# S7_LoRa.net
KiCad netlist of a schematic drawn in Altium Designer
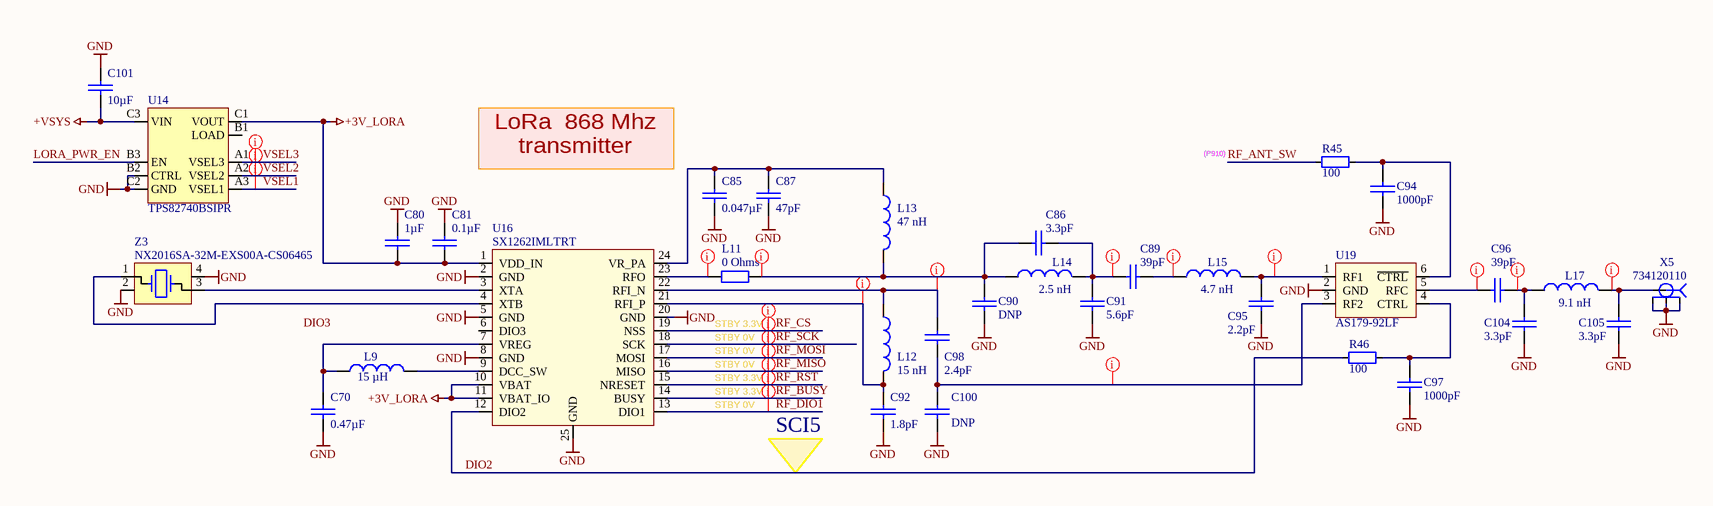
[diagram p0: S7_LoRa.SchDoc]

(export (version "E")
  (design (tool "Eeschema 10.0.6"))
  (components
    (comp (ref "C70")
      (value "0.47µF")
      (footprint "0402 CAP")
      (description "0.47µF, ±20%, 25V, X5R, 0402 (1005 Metric), -55°C ~ 85°C, -, Automotive")
      (fields
        (field (name "PART NUMBER") "GRT155R61E474ME01D")
        (field (name "MANUFACTURER") "Murata Electronics North America")
      )
      (libsource (lib "ea_PassivComps") (part "Capacitor"))
    )
    (comp (ref "C80")
      (value "1µF")
      (footprint "0402 CAP")
      (description "1µF, ±20%, 25V, X5R, 0402 (1005 Metric), -55°C ~ 85°C, -, General Purpose")
      (fields (field (name "PART NUMBER") "TMK105BJ105MV-F") (field (name "MANUFACTURER") "Taiyo Yuden"))
      (libsource (lib "ea_PassivComps") (part "Capacitor"))
    )
    (comp (ref "C81")
      (value "0.1µF")
      (footprint "0402 CAP")
      (description "0.1µF, ±10%, 50V, X7R, 0402 (1005 Metric), -55°C ~ 125°C, -, General Purpose")
      (fields
        (field (name "PART NUMBER") "0402B104K500CT")
        (field (name "MANUFACTURER") "Walsin Technology Corporation")
      )
      (libsource (lib "ea_PassivComps") (part "Capacitor"))
    )
    (comp (ref "C85")
      (value "0.047µF")
      (footprint "0402 CAP")
      (description "0.047µF, ±10%, 25V, X7R, 0402 (1005 Metric), -55°C ~ 125°C, -, General Purpose")
      (fields (field (name "PART NUMBER") "CC0402KRX7R8BB473") (field (name "MANUFACTURER") "Yageo"))
      (libsource (lib "ea_PassivComps") (part "Capacitor"))
    )
    (comp (ref "C86")
      (value "3.3pF")
      (footprint "0402 CAP")
      (description "3.3pF, ±0.1pF, 50V, C0G, NP0, 0402 (1005 Metric), -55°C ~ 125°C, -, RF, Microwave, High Frequency")
      (fields
        (field (name "PART NUMBER") "885392005011")
        (field (name "MANUFACTURER") "Wurth Electronics Inc.")
      )
      (libsource (lib "ea_PassivComps") (part "Capacitor"))
    )
    (comp (ref "C87")
      (value "47pF")
      (footprint "0402 CAP")
      (fields
        (field (name "PART NUMBER") "GJM1555C1H470FB01D")
        (field (name "MANUFACTURER") "Murata Electronics North America")
        (field (name "PARTNUM") "490-16376-1-ND")
      )
      (libsource (lib "ea_PassivComps") (part "Capacitor"))
    )
    (comp (ref "C89")
      (value "39pF")
      (footprint "0402 CAP")
      (fields
        (field (name "PART NUMBER") "GJM1555C1H390JB01D")
        (field (name "MANUFACTURER") "Murata Electronics North America")
        (field (name "PARTNUM") "490-17673-1-ND")
      )
      (libsource (lib "ea_PassivComps") (part "Capacitor"))
    )
    (comp (ref "C90")
      (value "DNP")
      (footprint "0402 CAP")
      (fields (field (name "Comment") "Capacitor_0402"))
      (libsource (lib "ea_Capacitors") (part "Capacitor_0402"))
    )
    (comp (ref "C91")
      (value "5.6pF")
      (footprint "0402 CAP")
      (fields
        (field (name "PART NUMBER") "GJM1555C1H5R6BB01D")
        (field (name "MANUFACTURER") "Murata Electronics North America")
        (field (name "PARTNUM") "490-11225-1-ND")
      )
      (libsource (lib "ea_PassivComps") (part "Capacitor"))
    )
    (comp (ref "C92")
      (value "1.8pF")
      (footprint "0402 CAP")
      (fields
        (field (name "PART NUMBER") "GJM1555C1H1R8BB01D")
        (field (name "MANUFACTURER") "Murata Electronics North America")
        (field (name "PARTNUM") "490-8089-1-ND")
      )
      (libsource (lib "ea_PassivComps") (part "Capacitor"))
    )
    (comp (ref "C94")
      (value "1000pF")
      (footprint "0402 CAP")
      (description "1000pF, ±5%, 50V, CH, 0402 (1005 Metric), -25°C ~ 85°C, Low ESL, General Purpose")
      (fields
        (field (name "PART NUMBER") "C1005CH1H102J050BA")
        (field (name "MANUFACTURER") "TDK Corporation")
      )
      (libsource (lib "ea_PassivComps") (part "Capacitor"))
    )
    (comp (ref "C95")
      (value "2.2pF")
      (footprint "0402 CAP")
      (fields
        (field (name "PART NUMBER") "CBR04C229B5GAC")
        (field (name "MANUFACTURER") "KEMET")
        (field (name "PARTNUM") "399-17527-1-ND")
      )
      (libsource (lib "ea_PassivComps") (part "Capacitor"))
    )
    (comp (ref "C96")
      (value "39pF")
      (footprint "0402 CAP")
      (fields
        (field (name "PART NUMBER") "GJM1555C1H390JB01D")
        (field (name "MANUFACTURER") "Murata Electronics North America")
        (field (name "PARTNUM") "490-17673-1-ND")
      )
      (libsource (lib "ea_PassivComps") (part "Capacitor"))
    )
    (comp (ref "C97")
      (value "1000pF")
      (footprint "0402 CAP")
      (description "1000pF, ±5%, 50V, CH, 0402 (1005 Metric), -25°C ~ 85°C, Low ESL, General Purpose")
      (fields
        (field (name "PART NUMBER") "C1005CH1H102J050BA")
        (field (name "MANUFACTURER") "TDK Corporation")
      )
      (libsource (lib "ea_PassivComps") (part "Capacitor"))
    )
    (comp (ref "C98")
      (value "2.4pF")
      (footprint "0402 CAP")
      (fields
        (field (name "PART NUMBER") "GJM1555C1H2R4BB01D")
        (field (name "MANUFACTURER") "Murata Electronics North America")
        (field (name "PARTNUM") "490-8093-1-ND")
      )
      (libsource (lib "ea_PassivComps") (part "Capacitor"))
    )
    (comp (ref "C100")
      (value "DNP")
      (footprint "0402 CAP")
      (fields (field (name "Comment") "Capacitor_0402"))
      (libsource (lib "ea_Capacitors") (part "Capacitor_0402"))
    )
    (comp (ref "C101")
      (value "10µF")
      (footprint "0603 CAP")
      (description "10µF, ±10%, 16V, X5R, 0603 (1608 Metric), -55°C ~ 85°C, -, Automotive")
      (fields
        (field (name "PART NUMBER") "GRT188R61C106KE13D")
        (field (name "MANUFACTURER") "Murata Electronics North America")
      )
      (libsource (lib "ea_PassivComps") (part "Capacitor"))
    )
    (comp (ref "C104")
      (value "3.3pF")
      (footprint "0402 CAP")
      (description "3.3pF, ±0.1pF, 50V, C0G, NP0, 0402 (1005 Metric), -55°C ~ 125°C, -, RF, Microwave, High Frequency")
      (fields
        (field (name "PART NUMBER") "885392005011")
        (field (name "MANUFACTURER") "Wurth Electronics Inc.")
      )
      (libsource (lib "ea_PassivComps") (part "Capacitor"))
    )
    (comp (ref "C105")
      (value "3.3pF")
      (footprint "0402 CAP")
      (description "3.3pF, ±0.1pF, 50V, C0G, NP0, 0402 (1005 Metric), -55°C ~ 125°C, -, RF, Microwave, High Frequency")
      (fields
        (field (name "PART NUMBER") "885392005011")
        (field (name "MANUFACTURER") "Wurth Electronics Inc.")
      )
      (libsource (lib "ea_PassivComps") (part "Capacitor"))
    )
    (comp (ref "L9")
      (value "15 µH")
      (footprint "2012[0805]")
      (description "15 µH Shielded Multilayer Inductor 250 mA, 1.235Ohm, 24MHz Max 0805 (2012 Metric)")
      (fields
        (field (name "MANUFACTURER") "Murata Electronics")
        (field (name "PARTNUM") "490-LQM21DH150M70LCT-ND")
      )
      (libsource (lib "ea_RF_inductors") (part "LQM21DH150M70L"))
    )
    (comp (ref "L11")
      (value "0 Ohms")
      (footprint "INDC1005-0402")
      (description "0 Ohms Jumper 0.063W, 1/16W Chip Resistor 0402 (1005 Metric) Automotive AEC-Q200 Thick Film")
      (fields (field (name "MANUFACTURER") "Vishay Dale") (field (name "PARTNUM") "541-0.0JCT-ND"))
      (libsource (lib "ea_RF_inductors") (part "CRCW04020000Z0ED"))
    )
    (comp (ref "L12")
      (value "15 nH")
      (footprint "INDC1005-0402")
      (description "15nH Unshielded Wirewound Inductor 460mA 160 mOhm Max 0402 (1006 Metric)")
      (fields (field (name "MANUFACTURER") "Murata") (field (name "TOLERANCE") "±3%"))
      (libsource (lib "ea_RF_inductors") (part "LQW15AN15NH00D"))
    )
    (comp (ref "L13")
      (value "47 nH")
      (footprint "INDC1005-0402")
      (description "47nH Unshielded Wirewound Inductor 210mA 1.08 Ohm Max 0402 (1005 Metric)")
      (fields (field (name "MANUFACTURER") "Murata") (field (name "TOLERANCE") "±5%"))
      (libsource (lib "ea_RF_inductors") (part "LQW15AN47NJ00D"))
    )
    (comp (ref "L14")
      (value "2.5 nH")
      (footprint "INDC1005-0402")
      (description "2.5nH Unshielded Wirewound Inductor 850mA 50 mOhm Max 0402 (1006 Metric)")
      (fields (field (name "MANUFACTURER") "Murata") (field (name "TOLERANCE") "±0.2nH"))
      (libsource (lib "ea_RF_inductors") (part "LQW15AN2N5C00D"))
    )
    (comp (ref "L15")
      (value "4.7 nH")
      (footprint "INDC1005-0402")
      (description "4.7nH Unshielded Wirewound Inductor 750mA 70 mOhm Max 0402 (1006 Metric)")
      (fields
        (field (name "MANUFACTURER") "Murata Electronics North America")
        (field (name "TOLERANCE") "±0.2nH")
      )
      (libsource (lib "ea_RF_inductors") (part "LQW15AN4N7C00D"))
    )
    (comp (ref "L17")
      (value "9.1 nH")
      (footprint "INDC1005-0402")
      (description "9.1nH Unshielded Wirewound Inductor 540mA 140 mOhm Max 0402 (1006 Metric)")
      (fields
        (field (name "MANUFACTURER") "Murata Electronics North America")
        (field (name "TOLERANCE") "±3%")
      )
      (libsource (lib "ea_RF_inductors") (part "LQW15AN9N1H00D"))
    )
    (comp (ref "R45")
      (value "100")
      (footprint "0402")
      (fields
        (field (name "MANUFACTURER") "Stackpole Electronics Inc")
        (field (name "TOLERANCE") "±1%")
        (field (name "VOLTAGE") "75V")
      )
      (libsource (lib "ea_PassivComps") (part "Resistor"))
    )
    (comp (ref "R46")
      (value "100")
      (footprint "0402")
      (fields
        (field (name "MANUFACTURER") "Stackpole Electronics Inc")
        (field (name "TOLERANCE") "±1%")
        (field (name "VOLTAGE") "75V")
      )
      (libsource (lib "ea_PassivComps") (part "Resistor"))
    )
    (comp (ref "U14")
      (value "TPS82740BSIPR")
      (footprint "MicroSiP")
      (fields (field (name "MANUFACTURER") "Texas Instruments") (field (name "PARTNUM") "296-46481-1-ND"))
      (libsource (lib "ea_IC_Power_Reg_Ref_Sw") (part "TPS82740BSIPR"))
    )
    (comp (ref "U16")
      (value "SX1262IMLTRT")
      (footprint "VQFN24")
      (description "IC RF TxRx Only General ISM < 1GHz LoRaWAN 150MHz ~ 960MHz 24-VFQFN Exposed Pad")
      (fields (field (name "MANUFACTURER") "Semtech Corporation"))
      (libsource (lib "ea_IC_RF") (part "SX1262IMLTRT"))
    )
    (comp (ref "U19")
      (value "AS179-92LF")
      (footprint "SC70-6")
      (description "RF Switch IC 802.11b, g, Bluetooth, WLAN SPDT 3 GHz 50Ohm SC-70-6, -40°C ~ 85°C")
      (fields
        (field (name "MANUFACTURER") "Skyworks Solutions Inc.")
        (field (name "PARTNUM") "863-1003-1-ND")
        (field (name "PARTNAME") "AS179-92LF")
      )
      (libsource (lib "ea_IC_RF") (part "AS179-92LF"))
    )
    (comp (ref "X5")
      (value "734120110")
      (footprint "0734120110")
      (description "U.FL (UMCC) Connector Receptacle, Male Pin 50 Ohm Surface Mount Solder")
      (fields (field (name "MANUFACTURER") "Molex") (field (name "PARTNUM") "WM5587TR-ND"))
      (libsource (lib "ea_Connectors_RF") (part "0734120110"))
    )
    (comp (ref "Z3")
      (value "NX2016SA-32M-EXS00A-CS06465")
      (footprint "4-SMD 2.00mm x 1.60mm")
      (description "32 MHz Crystal 10pF,  60 Ohms, 10 ppm,  4-SMD, No Lead, -40...+85 С")
      (fields (field (name "MANUFACTURER") "NDK America, Inc.") (field (name "PARTNUM") "644-1300-1-ND"))
      (libsource (lib "ea_OSC_CLK_GEN") (part "NX2016SA-32M-EXS00A-CS06465"))
    )
  )
  (nets
    (net (code "1") (name "+3V_LORA") (class "Default")
      (node (ref "C80") (pin "2") (pinfunction "2_2") (pintype "passive"))
      (node (ref "C81") (pin "2") (pinfunction "2_2") (pintype "passive"))
      (node (ref "U14") (pin "C1") (pinfunction "VOUT_C1") (pintype "passive"))
      (node (ref "U16") (pin "1") (pinfunction "VDD_IN_1") (pintype "power_in"))
      (node (ref "U16") (pin "10") (pinfunction "VBAT_10") (pintype "power_in"))
      (node (ref "U16") (pin "11") (pinfunction "VBAT_IO_11") (pintype "power_in"))
    )
    (net (code "2") (name "+VSYS") (class "Default")
      (node (ref "C101") (pin "2") (pinfunction "2_2") (pintype "passive"))
      (node (ref "U14") (pin "C3") (pinfunction "VIN_C3") (pintype "passive"))
    )
    (net (code "3") (name "/DIO2") (class "Default")
      (node (ref "R46") (pin "2") (pinfunction "2_2") (pintype "passive"))
      (node (ref "U16") (pin "12") (pinfunction "DIO2_12") (pintype "passive"))
    )
    (net (code "5") (name "/LORA_PWR_EN") (class "Default")
      (node (ref "U14") (pin "B3") (pinfunction "EN_B3") (pintype "passive"))
    )
    (net (code "6") (name "/RF_ANT_SW") (class "Default")
      (node (ref "R45") (pin "2") (pinfunction "2_2") (pintype "passive"))
    )
    (net (code "7") (name "/RF_BUSY") (class "Default")
      (node (ref "U16") (pin "14") (pinfunction "BUSY_14") (pintype "passive"))
    )
    (net (code "8") (name "/RF_CS") (class "Default")
      (node (ref "U16") (pin "19") (pinfunction "NSS_19") (pintype "passive"))
    )
    (net (code "9") (name "/RF_DIO1") (class "Default")
      (node (ref "U16") (pin "13") (pinfunction "DIO1_13") (pintype "passive"))
    )
    (net (code "10") (name "/RF_MISO") (class "Default")
      (node (ref "U16") (pin "16") (pinfunction "MISO_16") (pintype "passive"))
    )
    (net (code "11") (name "/RF_MOSI") (class "Default")
      (node (ref "U16") (pin "17") (pinfunction "MOSI_17") (pintype "passive"))
    )
    (net (code "12") (name "/RF_RST") (class "Default")
      (node (ref "U16") (pin "15") (pinfunction "NRESET_15") (pintype "passive"))
    )
    (net (code "13") (name "/RF_SCK") (class "Default")
      (node (ref "U16") (pin "18") (pinfunction "SCK_18") (pintype "passive"))
    )
    (net (code "14") (name "/VSEL1") (class "Default")
      (node (ref "U14") (pin "A3") (pinfunction "VSEL1_A3") (pintype "passive"))
    )
    (net (code "15") (name "/VSEL2") (class "Default")
      (node (ref "U14") (pin "A2") (pinfunction "VSEL2_A2") (pintype "passive"))
    )
    (net (code "16") (name "/VSEL3") (class "Default")
      (node (ref "U14") (pin "A1") (pinfunction "VSEL3_A1") (pintype "passive"))
    )
    (net (code "17") (name "GND") (class "Default")
      (node (ref "C100") (pin "2") (pinfunction "2_2") (pintype "passive"))
      (node (ref "C101") (pin "1") (pinfunction "1_1") (pintype "passive"))
      (node (ref "C104") (pin "1") (pinfunction "1_1") (pintype "passive"))
      (node (ref "C105") (pin "1") (pinfunction "1_1") (pintype "passive"))
      (node (ref "C70") (pin "2") (pinfunction "2_2") (pintype "passive"))
      (node (ref "C80") (pin "1") (pinfunction "1_1") (pintype "passive"))
      (node (ref "C81") (pin "1") (pinfunction "1_1") (pintype "passive"))
      (node (ref "C85") (pin "2") (pinfunction "2_2") (pintype "passive"))
      (node (ref "C87") (pin "2") (pinfunction "2_2") (pintype "passive"))
      (node (ref "C90") (pin "2") (pinfunction "2_2") (pintype "passive"))
      (node (ref "C91") (pin "2") (pinfunction "2_2") (pintype "passive"))
      (node (ref "C92") (pin "2") (pinfunction "2_2") (pintype "passive"))
      (node (ref "C94") (pin "1") (pinfunction "1_1") (pintype "passive"))
      (node (ref "C95") (pin "2") (pinfunction "2_2") (pintype "passive"))
      (node (ref "C97") (pin "1") (pinfunction "1_1") (pintype "passive"))
      (node (ref "U14") (pin "B2") (pinfunction "CTRL_B2") (pintype "passive"))
      (node (ref "U14") (pin "C2") (pinfunction "GND_C2") (pintype "passive"))
      (node (ref "U16") (pin "2") (pinfunction "GND_2") (pintype "passive"))
      (node (ref "U16") (pin "20") (pinfunction "GND_20") (pintype "passive"))
      (node (ref "U16") (pin "25") (pinfunction "GND_25") (pintype "passive"))
      (node (ref "U16") (pin "5") (pinfunction "GND_5") (pintype "passive"))
      (node (ref "U16") (pin "8") (pinfunction "GND_8") (pintype "passive"))
      (node (ref "U19") (pin "2") (pinfunction "GND_2") (pintype "passive"))
      (node (ref "X5") (pin "2") (pinfunction "2_2") (pintype "passive"))
      (node (ref "X5") (pin "3") (pinfunction "3_3") (pintype "passive"))
      (node (ref "X5") (pin "4") (pinfunction "3_4") (pintype "passive"))
      (node (ref "Z3") (pin "2") (pinfunction "2_2") (pintype "passive"))
      (node (ref "Z3") (pin "4") (pinfunction "4_4") (pintype "passive"))
    )
    (net (code "18") (name "Net-(C86-Pad1)") (class "Default")
      (node (ref "C86") (pin "1") (pinfunction "1_1") (pintype "passive"))
      (node (ref "C90") (pin "1") (pinfunction "1_1") (pintype "passive"))
      (node (ref "L11") (pin "2") (pinfunction "2_2") (pintype "passive"))
      (node (ref "L13") (pin "2") (pinfunction "2_2") (pintype "passive"))
      (node (ref "L14") (pin "1") (pinfunction "1_1") (pintype "passive"))
    )
    (net (code "19") (name "Net-(C86-Pad2)") (class "Default")
      (node (ref "C86") (pin "2") (pinfunction "2_2") (pintype "passive"))
      (node (ref "C89") (pin "1") (pinfunction "1_1") (pintype "passive"))
      (node (ref "C91") (pin "1") (pinfunction "1_1") (pintype "passive"))
      (node (ref "L14") (pin "2") (pinfunction "2_2") (pintype "passive"))
    )
    (net (code "20") (name "Net-(C89-Pad2)") (class "Default")
      (node (ref "C89") (pin "2") (pinfunction "2_2") (pintype "passive"))
      (node (ref "L15") (pin "1") (pinfunction "1_1") (pintype "passive"))
    )
    (net (code "21") (name "Net-(C104-Pad2)") (class "Default")
      (node (ref "C104") (pin "2") (pinfunction "2_2") (pintype "passive"))
      (node (ref "C96") (pin "2") (pinfunction "2_2") (pintype "passive"))
      (node (ref "L17") (pin "1") (pinfunction "1_1") (pintype "passive"))
    )
    (net (code "22") (name "Net-(U16-DCC_SW)") (class "Default")
      (node (ref "L9") (pin "2") (pinfunction "2_2") (pintype "passive"))
      (node (ref "U16") (pin "9") (pinfunction "DCC_SW_9") (pintype "power_in"))
    )
    (net (code "23") (name "Net-(U16-RFI_N)") (class "Default")
      (node (ref "C98") (pin "1") (pinfunction "1_1") (pintype "passive"))
      (node (ref "L12") (pin "1") (pinfunction "1_1") (pintype "passive"))
      (node (ref "U16") (pin "22") (pinfunction "RFI_N_22") (pintype "passive"))
    )
    (net (code "24") (name "Net-(U16-RFI_P)") (class "Default")
      (node (ref "C92") (pin "1") (pinfunction "1_1") (pintype "passive"))
      (node (ref "L12") (pin "2") (pinfunction "2_2") (pintype "passive"))
      (node (ref "U16") (pin "21") (pinfunction "RFI_P_21") (pintype "passive"))
    )
    (net (code "25") (name "Net-(U16-RFO)") (class "Default")
      (node (ref "L11") (pin "1") (pinfunction "1_1") (pintype "passive"))
      (node (ref "U16") (pin "23") (pinfunction "RFO_23") (pintype "passive"))
    )
    (net (code "26") (name "Net-(U16-VREG)") (class "Default")
      (node (ref "C70") (pin "1") (pinfunction "1_1") (pintype "passive"))
      (node (ref "L9") (pin "1") (pinfunction "1_1") (pintype "passive"))
      (node (ref "U16") (pin "7") (pinfunction "VREG_7") (pintype "power_in"))
    )
    (net (code "27") (name "Net-(U16-VR_PA)") (class "Default")
      (node (ref "C85") (pin "1") (pinfunction "1_1") (pintype "passive"))
      (node (ref "C87") (pin "1") (pinfunction "1_1") (pintype "passive"))
      (node (ref "L13") (pin "1") (pinfunction "1_1") (pintype "passive"))
      (node (ref "U16") (pin "24") (pinfunction "VR_PA_24") (pintype "power_in"))
    )
    (net (code "28") (name "Net-(U16-XTA)") (class "Default")
      (node (ref "U16") (pin "3") (pinfunction "XTA_3") (pintype "passive"))
      (node (ref "Z3") (pin "3") (pintype "passive"))
    )
    (net (code "29") (name "Net-(U16-XTB)") (class "Default")
      (node (ref "U16") (pin "4") (pinfunction "XTB_4") (pintype "passive"))
      (node (ref "Z3") (pin "1") (pinfunction "1_1") (pintype "passive"))
    )
    (net (code "30") (name "Net-(U19-CTRL)") (class "Default")
      (node (ref "C97") (pin "2") (pinfunction "2_2") (pintype "passive"))
      (node (ref "R46") (pin "1") (pinfunction "1_1") (pintype "passive"))
      (node (ref "U19") (pin "4") (pinfunction "CTRL_4") (pintype "passive"))
    )
    (net (code "31") (name "Net-(U19-RF1)") (class "Default")
      (node (ref "C95") (pin "1") (pinfunction "1_1") (pintype "passive"))
      (node (ref "L15") (pin "2") (pinfunction "2_2") (pintype "passive"))
      (node (ref "U19") (pin "1") (pinfunction "RF1_1") (pintype "passive"))
    )
    (net (code "32") (name "Net-(U19-RF2)") (class "Default")
      (node (ref "C100") (pin "1") (pinfunction "1_1") (pintype "passive"))
      (node (ref "C98") (pin "2") (pinfunction "2_2") (pintype "passive"))
      (node (ref "U19") (pin "3") (pinfunction "RF2_3") (pintype "passive"))
    )
    (net (code "33") (name "Net-(U19-RFC)") (class "Default")
      (node (ref "C96") (pin "1") (pinfunction "1_1") (pintype "passive"))
      (node (ref "U19") (pin "5") (pinfunction "RFC_5") (pintype "passive"))
    )
    (net (code "34") (name "Net-(U19-~{CTRL})") (class "Default")
      (node (ref "C94") (pin "2") (pinfunction "2_2") (pintype "passive"))
      (node (ref "R45") (pin "1") (pinfunction "1_1") (pintype "passive"))
      (node (ref "U19") (pin "6") (pinfunction "~{CTRL}_6") (pintype "passive"))
    )
    (net (code "35") (name "Net-(X5-Sig)") (class "Default")
      (node (ref "C105") (pin "2") (pinfunction "2_2") (pintype "passive"))
      (node (ref "L17") (pin "2") (pinfunction "2_2") (pintype "passive"))
      (node (ref "X5") (pin "1") (pinfunction "Sig_1") (pintype "passive"))
    )
    (net (code "36") (name "unconnected-(U14-LOAD-PadB1)") (class "Default")
      (node (ref "U14") (pin "B1") (pinfunction "LOAD_B1") (pintype "passive"))
    )
    (net (code "37") (name "unconnected-(U16-DIO3-Pad6)") (class "Default")
      (node (ref "U16") (pin "6") (pinfunction "DIO3_6") (pintype "passive"))
    )
  )
)
